# Power_HUMA-mini.net
KiCad netlist of a schematic drawn in Altium Designer
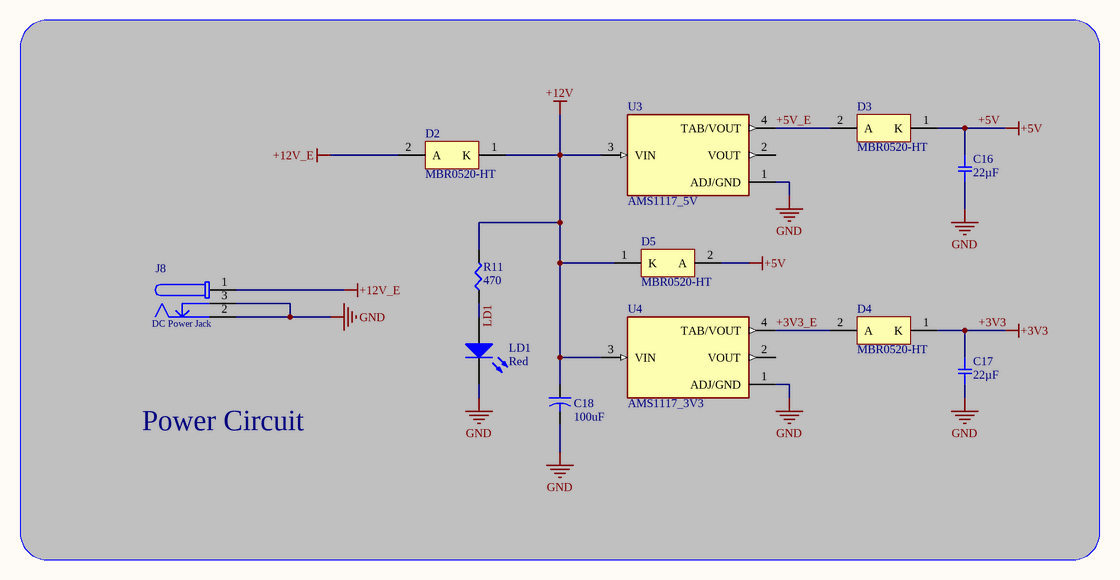
[diagram p0: Power_HUMA-mini.SchDoc]

(export (version "E")
  (design (tool "Eeschema 10.0.6"))
  (components
    (comp (ref "C16")
      (value "22µF")
      (footprint "SMD-1206C")
      (description "CAP CER 22UF 10V X7R 1206")
      (fields
        (field (name "DIGI-KEY PART NUMBER") "490-6516-1-ND")
        (field (name "PART NUMBER") "GRM31CR71A226ME15L")
      )
      (libsource (lib "Capacitors_Murata") (part "GRM31CR71A226ME15L"))
    )
    (comp (ref "C17")
      (value "22µF")
      (footprint "SMD-1206C")
      (description "CAP CER 22UF 10V X7R 1206")
      (fields
        (field (name "DIGI-KEY PART NUMBER") "490-6516-1-ND")
        (field (name "PART NUMBER") "GRM31CR71A226ME15L")
      )
      (libsource (lib "Capacitors_Murata") (part "GRM31CR71A226ME15L"))
    )
    (comp (ref "C18")
      (value "100uF")
      (footprint "CAPR5-4X5")
      (description "Capacitor")
      (fields (field (name "Comment") "Cap2") (field (name "PUBLISHER") "Altium Limited"))
      (libsource (lib "Miscellaneous Devices") (part "Cap2"))
    )
    (comp (ref "D2")
      (value "MBR0520-HT")
      (footprint "ONSC-SOD-123-2-425-04_V")
      (description "20V 0.5A Schottky Power Rectifier, 2-Pin SOD-123, Tape and Reel")
      (fields (field (name "MANUFACTURER") "On Semiconductor") (field (name "PARTNUMBER") "MBR0520LT1"))
      (libsource (lib "") (part "MBR0520LT1_1"))
    )
    (comp (ref "D3")
      (value "MBR0520-HT")
      (footprint "ONSC-SOD-123-2-425-04_V")
      (description "20V 0.5A Schottky Power Rectifier, 2-Pin SOD-123, Tape and Reel")
      (fields (field (name "MANUFACTURER") "On Semiconductor") (field (name "PARTNUMBER") "MBR0520LT1"))
      (libsource (lib "") (part "MBR0520LT1_1"))
    )
    (comp (ref "D4")
      (value "MBR0520-HT")
      (footprint "ONSC-SOD-123-2-425-04_V")
      (description "20V 0.5A Schottky Power Rectifier, 2-Pin SOD-123, Tape and Reel")
      (fields (field (name "MANUFACTURER") "On Semiconductor") (field (name "PARTNUMBER") "MBR0520LT1"))
      (libsource (lib "") (part "MBR0520LT1_1"))
    )
    (comp (ref "D5")
      (value "MBR0520-HT")
      (footprint "ONSC-SOD-123-2-425-04_V")
      (description "20V 0.5A Schottky Power Rectifier, 2-Pin SOD-123, Tape and Reel")
      (fields (field (name "MANUFACTURER") "On Semiconductor") (field (name "PARTNUMBER") "MBR0520LT1"))
      (libsource (lib "ON Semi Schottky Diodes & Schottky Rectifiers") (part "MBR0520LT1"))
    )
    (comp (ref "J8")
      (value "DC Power Jack")
      (footprint "694106301002")
      (description "DC Power Jack Connector WR-DC, Male, Right Angled, THT, 5 A, 24 V")
      (fields (field (name "PART NUMBER") "694106301002") (field (name "PUBLISHER") "Wurth Elektronik"))
      (libsource (lib "WR-DC_Power_Jack_Connectors") (part "694106301002"))
    )
    (comp (ref "LD1")
      (value "Red")
      (footprint "Type 3mm")
      (description "THT LED round mono-color waterclear, WL-TMRW, Red")
      (fields (field (name "PARTNUMBER") "151033RS03000"))
      (libsource (lib "WL-TMRW THT LED round mono-color waterclear") (part "151033RS03000"))
    )
    (comp (ref "R11")
      (value "470")
      (footprint "SMD-0805-RES")
      (description "RES SMD 470 OHM 5% 1/2W 0805")
      (fields (field (name "PART NUMBER") "ERJ-P6WJ471V") (field (name "DIGI-KEY PART NUMBER") "P16950CT-ND"))
      (libsource (lib "Resistors_Panasonic") (part "ERJ-P6WJ471V"))
    )
    (comp (ref "U3")
      (value "AMS1117_5V")
      (footprint "*SOT229P700X180-4N")
      (description "Sot223/Pkg 1-Amp Low Drop Out Voltage Regulator")
      (fields (field (name "MF") "Advanced Monolithic Systems") (field (name "MP") "AMS1117-3.3"))
      (libsource (lib "AMS1117") (part "AMS1117"))
    )
    (comp (ref "U4")
      (value "AMS1117_3V3")
      (footprint "*SOT229P700X180-4N")
      (description "Sot223/Pkg 1-Amp Low Drop Out Voltage Regulator")
      (fields (field (name "MF") "Advanced Monolithic Systems") (field (name "MP") "AMS1117-3.3"))
      (libsource (lib "AMS1117") (part "AMS1117"))
    )
  )
  (nets
    (net (code "1") (name "+3V3") (class "Default")
      (node (ref "C17") (pin "1") (pinfunction "1_1") (pintype "passive"))
      (node (ref "D4") (pin "1") (pinfunction "K_1") (pintype "passive"))
    )
    (net (code "2") (name "+5V") (class "Default")
      (node (ref "C16") (pin "1") (pinfunction "1_1") (pintype "passive"))
      (node (ref "D3") (pin "1") (pinfunction "K_1") (pintype "passive"))
      (node (ref "D5") (pin "2") (pinfunction "A_2") (pintype "passive"))
    )
    (net (code "3") (name "+12V") (class "Default")
      (node (ref "C18") (pin "1") (pinfunction "1_1") (pintype "passive"))
      (node (ref "D2") (pin "1") (pinfunction "K_1") (pintype "passive"))
      (node (ref "D5") (pin "1") (pinfunction "K_1") (pintype "passive"))
      (node (ref "R11") (pin "2") (pinfunction "2_2") (pintype "passive"))
      (node (ref "U3") (pin "3") (pinfunction "VIN_3") (pintype "input"))
      (node (ref "U4") (pin "3") (pinfunction "VIN_3") (pintype "input"))
    )
    (net (code "4") (name "+12V_E") (class "Default")
      (node (ref "D2") (pin "2") (pinfunction "A_2") (pintype "passive"))
      (node (ref "J8") (pin "1") (pinfunction "1_1") (pintype "passive"))
    )
    (net (code "5") (name "/+3V3_E") (class "Default")
      (node (ref "D4") (pin "2") (pinfunction "A_2") (pintype "passive"))
      (node (ref "U4") (pin "4") (pinfunction "TAB/VOUT_4") (pintype "output"))
    )
    (net (code "6") (name "/+5V_E") (class "Default")
      (node (ref "D3") (pin "2") (pinfunction "A_2") (pintype "passive"))
      (node (ref "U3") (pin "4") (pinfunction "TAB/VOUT_4") (pintype "output"))
    )
    (net (code "7") (name "/LD1") (class "Default")
      (node (ref "LD1") (pin "2") (pinfunction "A_2") (pintype "passive"))
      (node (ref "R11") (pin "1") (pinfunction "1_1") (pintype "passive"))
    )
    (net (code "8") (name "GND") (class "Default")
      (node (ref "C16") (pin "2") (pinfunction "2_2") (pintype "passive"))
      (node (ref "C17") (pin "2") (pinfunction "2_2") (pintype "passive"))
      (node (ref "C18") (pin "2") (pinfunction "2_2") (pintype "passive"))
      (node (ref "J8") (pin "2") (pinfunction "2_2") (pintype "passive"))
      (node (ref "J8") (pin "3") (pinfunction "3_3") (pintype "passive"))
      (node (ref "LD1") (pin "1") (pinfunction "K_1") (pintype "passive"))
      (node (ref "U3") (pin "1") (pinfunction "ADJ/GND_1") (pintype "power_in"))
      (node (ref "U4") (pin "1") (pinfunction "ADJ/GND_1") (pintype "power_in"))
    )
    (net (code "9") (name "unconnected-(U3-VOUT-Pad2)") (class "Default")
      (node (ref "U3") (pin "2") (pinfunction "VOUT_2") (pintype "output"))
    )
    (net (code "10") (name "unconnected-(U4-VOUT-Pad2)") (class "Default")
      (node (ref "U4") (pin "2") (pinfunction "VOUT_2") (pintype "output"))
    )
  )
)
